# can.net
KiCad netlist of a schematic drawn in Altium Designer
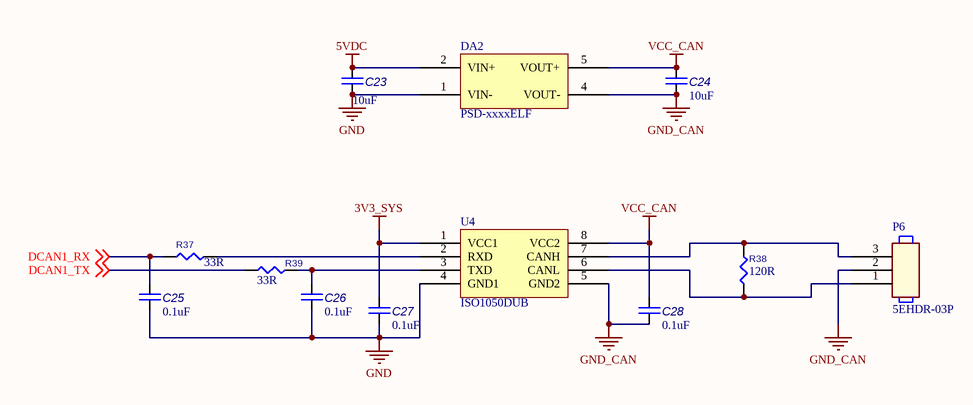
[diagram p0: can.SchDoc]

(export (version "E")
  (design (tool "Eeschema 10.0.6"))
  (components
    (comp (ref "C23")
      (value "10uF")
      (footprint "CC2012-0805")
      (description "C0805")
      (libsource (lib "pmvent") (part "C0805"))
    )
    (comp (ref "C24")
      (value "10uF")
      (footprint "CC2012-0805")
      (description "C0805")
      (libsource (lib "pmvent") (part "C0805"))
    )
    (comp (ref "C25")
      (value "0.1uF")
      (footprint "CC1608-0603")
      (description "C0603")
      (libsource (lib "spider") (part "C0603"))
    )
    (comp (ref "C26")
      (value "0.1uF")
      (footprint "CC1608-0603")
      (description "C0603")
      (libsource (lib "spider") (part "C0603"))
    )
    (comp (ref "C27")
      (value "0.1uF")
      (footprint "CC1608-0603")
      (description "C0603")
      (libsource (lib "spider") (part "C0603"))
    )
    (comp (ref "C28")
      (value "0.1uF")
      (footprint "CC1608-0603")
      (description "C0603")
      (libsource (lib "spider") (part "C0603"))
    )
    (comp (ref "DA2")
      (value "PSD-xxxxELF")
      (footprint "PSD-xxxxELF")
      (description "single output isolated DC/DC converter")
      (fields (field (name "MANUFACTURER") "PEAK electronics"))
      (libsource (lib "pmvent") (part "PSD-xxxxELF"))
    )
    (comp (ref "P6")
      (value "TE_282814-3")
      (footprint "TE_282814-3")
      (description "Terminal Block Connectors")
      (fields (field (name "P/N") "5EHDR-03P"))
      (libsource (lib "pmvent") (part "TE_282814-3"))
    )
    (comp (ref "R37")
      (value "33R")
      (footprint "RESC1608X55N")
      (description "R0603")
      (libsource (lib "pmvent") (part "R0603"))
    )
    (comp (ref "R38")
      (value "120R")
      (footprint "RESC1608X55N")
      (description "R0603")
      (libsource (lib "pmvent") (part "R0603"))
    )
    (comp (ref "R39")
      (value "33R")
      (footprint "RESC1608X55N")
      (description "R0603")
      (libsource (lib "pmvent") (part "R0603"))
    )
    (comp (ref "U4")
      (value "ISO1050DUB")
      (footprint "SO-G8/Z10.8")
      (description "ISOLATED CAN TRANSCEIVER")
      (fields (field (name "MANUFACTURER") "TI"))
      (libsource (lib "pmvent") (part "ISO1050DUB"))
    )
  )
  (nets
    (net (code "1") (name "3V3_SYS") (class "Default")
      (node (ref "C27") (pin "1") (pinfunction "1_1") (pintype "passive"))
      (node (ref "U4") (pin "1") (pinfunction "VCC1_1") (pintype "passive"))
    )
    (net (code "2") (name "5VDC") (class "Default")
      (node (ref "C23") (pin "2") (pinfunction "2_2") (pintype "passive"))
      (node (ref "DA2") (pin "2") (pinfunction "VIN+_2") (pintype "passive"))
    )
    (net (code "3") (name "DCAN1_RX") (class "Default")
      (node (ref "C25") (pin "1") (pinfunction "1_1") (pintype "passive"))
      (node (ref "R37") (pin "2") (pinfunction "2_2") (pintype "passive"))
    )
    (net (code "4") (name "DCAN1_TX") (class "Default")
      (node (ref "R39") (pin "2") (pinfunction "2_2") (pintype "passive"))
    )
    (net (code "5") (name "GND") (class "Default")
      (node (ref "C23") (pin "1") (pinfunction "1_1") (pintype "passive"))
      (node (ref "C25") (pin "2") (pinfunction "2_2") (pintype "passive"))
      (node (ref "C26") (pin "2") (pinfunction "2_2") (pintype "passive"))
      (node (ref "C27") (pin "2") (pinfunction "2_2") (pintype "passive"))
      (node (ref "DA2") (pin "1") (pinfunction "VIN-_1") (pintype "passive"))
      (node (ref "U4") (pin "4") (pinfunction "GND1_4") (pintype "passive"))
    )
    (net (code "6") (name "GND_CAN") (class "Default")
      (node (ref "C24") (pin "1") (pinfunction "1_1") (pintype "passive"))
      (node (ref "C28") (pin "2") (pinfunction "2_2") (pintype "passive"))
      (node (ref "DA2") (pin "4") (pinfunction "VOUT-_4") (pintype "passive"))
      (node (ref "P6") (pin "2") (pinfunction "2_2") (pintype "passive"))
      (node (ref "U4") (pin "5") (pinfunction "GND2_5") (pintype "passive"))
    )
    (net (code "7") (name "Net-(U4-CANH)") (class "Default")
      (node (ref "P6") (pin "3") (pinfunction "3_3") (pintype "passive"))
      (node (ref "R38") (pin "2") (pinfunction "2_2") (pintype "passive"))
      (node (ref "U4") (pin "7") (pinfunction "CANH_7") (pintype "passive"))
    )
    (net (code "8") (name "Net-(U4-CANL)") (class "Default")
      (node (ref "P6") (pin "1") (pinfunction "1_1") (pintype "passive"))
      (node (ref "R38") (pin "1") (pinfunction "1_1") (pintype "passive"))
      (node (ref "U4") (pin "6") (pinfunction "CANL_6") (pintype "passive"))
    )
    (net (code "9") (name "Net-(U4-RXD)") (class "Default")
      (node (ref "R37") (pin "1") (pinfunction "1_1") (pintype "passive"))
      (node (ref "U4") (pin "2") (pinfunction "RXD_2") (pintype "passive"))
    )
    (net (code "10") (name "Net-(U4-TXD)") (class "Default")
      (node (ref "C26") (pin "1") (pinfunction "1_1") (pintype "passive"))
      (node (ref "R39") (pin "1") (pinfunction "1_1") (pintype "passive"))
      (node (ref "U4") (pin "3") (pinfunction "TXD_3") (pintype "passive"))
    )
    (net (code "11") (name "VCC_CAN") (class "Default")
      (node (ref "C24") (pin "2") (pinfunction "2_2") (pintype "passive"))
      (node (ref "C28") (pin "1") (pinfunction "1_1") (pintype "passive"))
      (node (ref "DA2") (pin "5") (pinfunction "VOUT+_5") (pintype "passive"))
      (node (ref "U4") (pin "8") (pinfunction "VCC2_8") (pintype "passive"))
    )
  )
)
